# IO_bottom_board.net
KiCad netlist of a schematic drawn in EAGLE
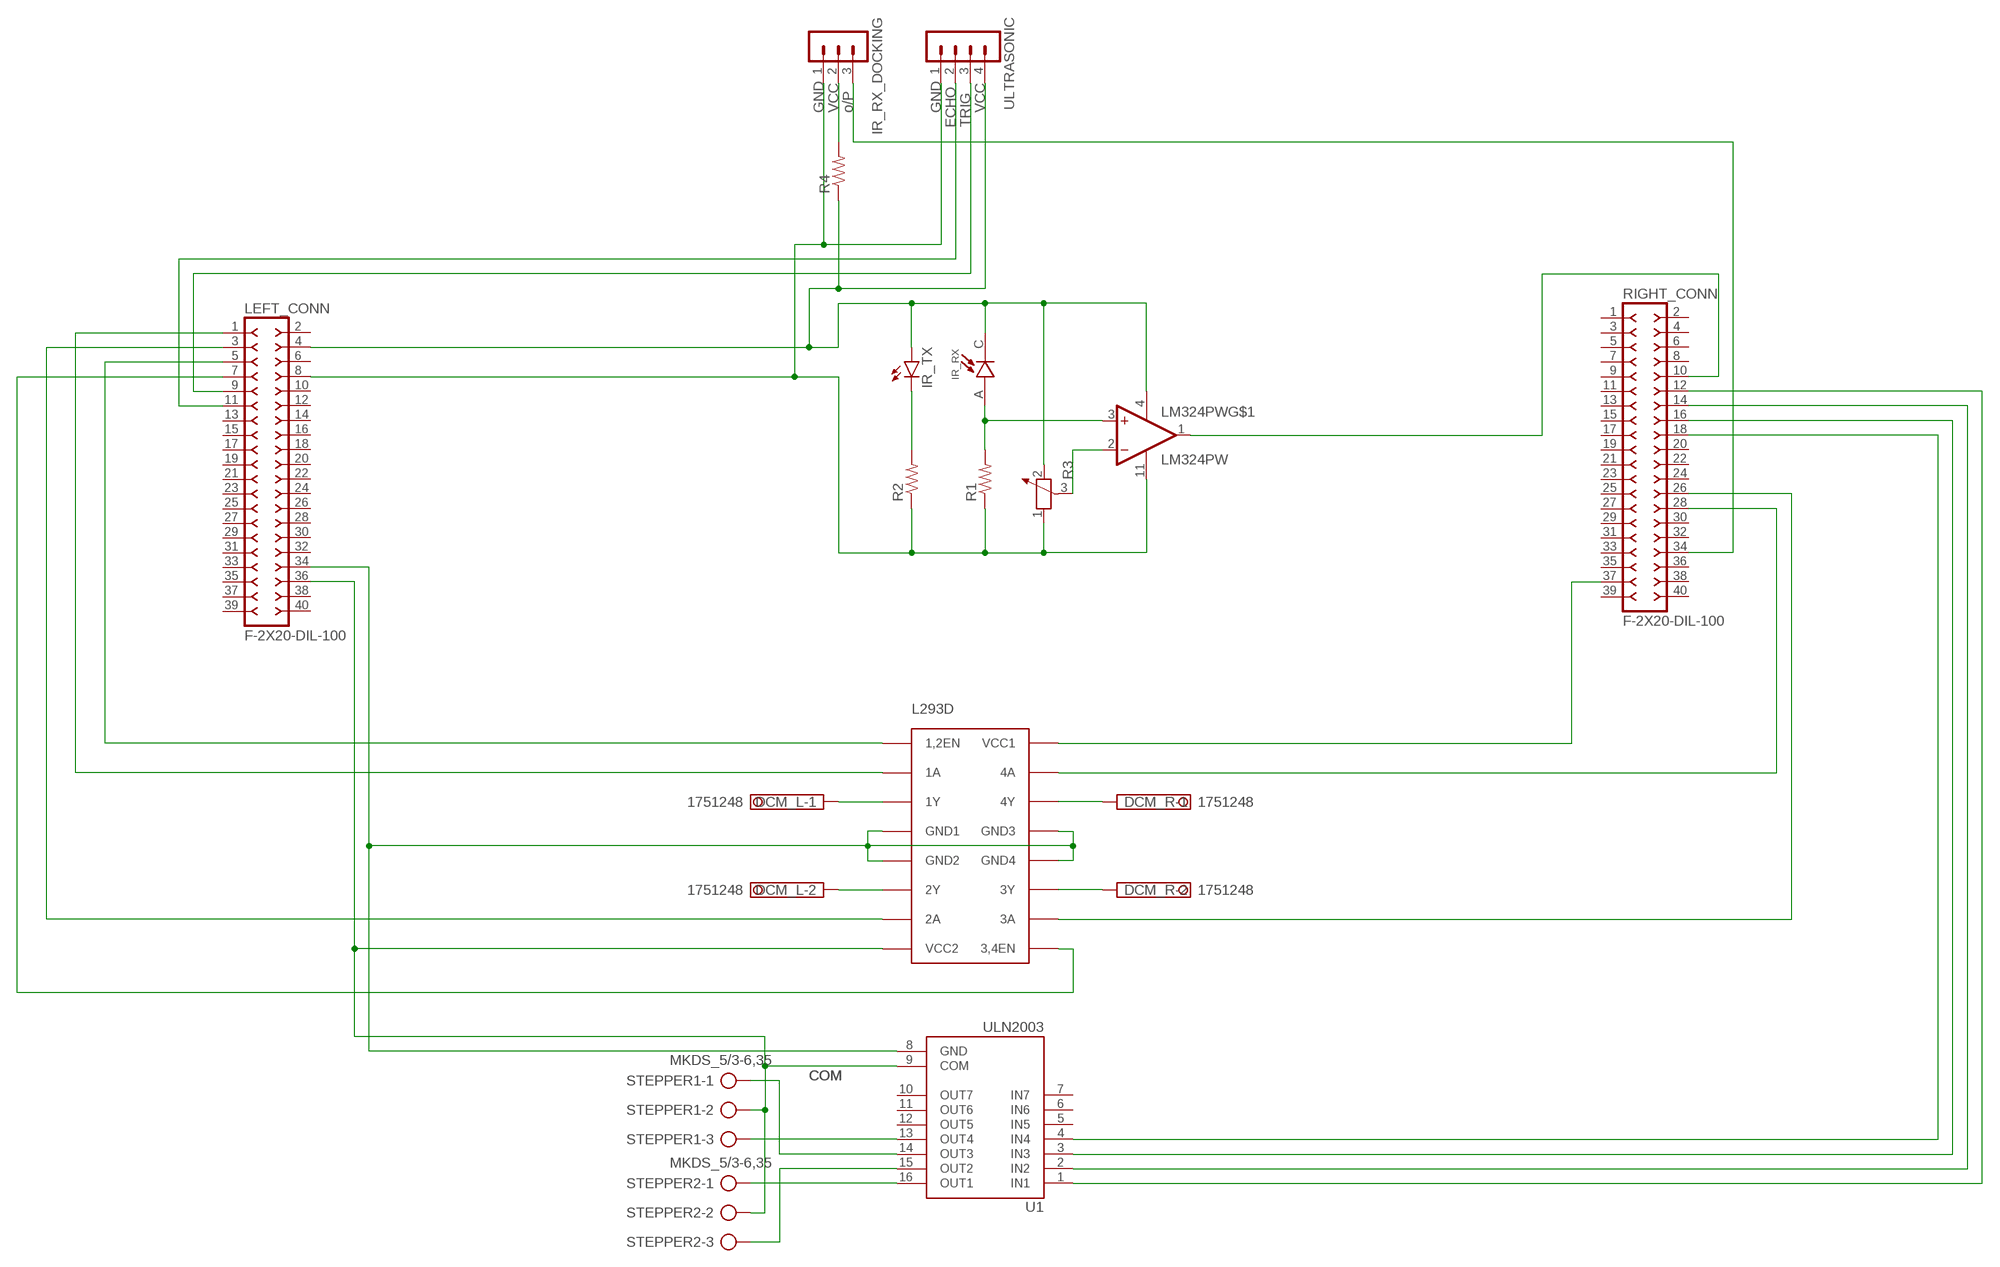
[diagram p0: schematic, sheet 1]

(export (version "E")
  (design (tool "Eeschema 10.0.6"))
  (components
    (comp (ref "DCM_L")
      (value "1751248")
      (footprint "eagle-import:1751248")
      (libsource (lib "eagle-import") (part "1751248"))
    )
    (comp (ref "DCM_R")
      (value "1751248")
      (footprint "eagle-import:1751248")
      (libsource (lib "eagle-import") (part "1751248"))
    )
    (comp (ref "IR_RX")
      (value "BPV10")
      (footprint "eagle-import:XDCR_BPV10")
      (fields (field (name "MF") "Vishay"))
      (libsource (lib "eagle-import") (part "BPV10"))
    )
    (comp (ref "IR_RX_DOCKING")
      (value "MA03-1")
      (footprint "eagle-import:MA03-1")
      (libsource (lib "eagle-import") (part "MA03-1"))
    )
    (comp (ref "IR_TX")
      (value "SFH482")
      (footprint "eagle-import:SFH482")
      (libsource (lib "eagle-import") (part "SFH482"))
    )
    (comp (ref "L293D")
      (value "L293D")
      (footprint "eagle-import:DIL16")
      (libsource (lib "eagle-import") (part "L293D"))
    )
    (comp (ref "LEFT_CONN")
      (value "F-2X20-DIL-100")
      (footprint "eagle-import:DIL-100-2X20")
      (libsource (lib "eagle-import") (part "F-2X20-DIL-100"))
    )
    (comp (ref "LM324PW")
      (value "LM324PW")
      (footprint "eagle-import:SOP65P640X120-14N")
      (fields (field (name "MF") "Texas Instruments"))
      (libsource (lib "eagle-import") (part "LM324PW"))
    )
    (comp (ref "R1")
      (value "R-US_0204/5")
      (footprint "eagle-import:0204_5")
      (libsource (lib "eagle-import") (part "R-US_0204/5"))
    )
    (comp (ref "R2")
      (value "R-US_0204/5")
      (footprint "eagle-import:0204_5")
      (libsource (lib "eagle-import") (part "R-US_0204/5"))
    )
    (comp (ref "R3")
      (value "POTENTIOMETER_PT-10")
      (footprint "eagle-import:PT-10")
      (libsource (lib "eagle-import") (part "POTENTIOMETER_PT-10"))
    )
    (comp (ref "R4")
      (value "R-US_0204/5")
      (footprint "eagle-import:0204_5")
      (libsource (lib "eagle-import") (part "R-US_0204/5"))
    )
    (comp (ref "RIGHT_CONN")
      (value "F-2X20-DIL-100")
      (footprint "eagle-import:DIL-100-2X20")
      (libsource (lib "eagle-import") (part "F-2X20-DIL-100"))
    )
    (comp (ref "STEPPER1")
      (value "MKDS_5/3-6,35")
      (footprint "eagle-import:MKDS_5_3-635")
      (fields (field (name "MF") "FARNELL") (field (name "MPN") "1714968"))
      (libsource (lib "eagle-import") (part "MKDS_5/3-6,35"))
    )
    (comp (ref "STEPPER2")
      (value "MKDS_5/3-6,35")
      (footprint "eagle-import:MKDS_5_3-635")
      (fields (field (name "MF") "FARNELL") (field (name "MPN") "1714968"))
      (libsource (lib "eagle-import") (part "MKDS_5/3-6,35"))
    )
    (comp (ref "U1")
      (value "ULN2003")
      (footprint "eagle-import:DIP762W46P254L1969H533Q16")
      (fields (field (name "MF") "STMicroelectronics"))
      (libsource (lib "eagle-import") (part "ULN2003"))
    )
    (comp (ref "ULTRASONIC")
      (value "MA04-1")
      (footprint "eagle-import:MA04-1")
      (libsource (lib "eagle-import") (part "MA04-1"))
    )
  )
  (nets
    (net (code "1") (name "Net-(DCM_LA-K)") (class "Default")
      (node (ref "DCM_L") (pin "1") (pinfunction "K_1") (pintype "passive"))
      (node (ref "L293D") (pin "3") (pinfunction "1Y_3") (pintype "output"))
    )
    (net (code "2") (name "Net-(DCM_LB-K)") (class "Default")
      (node (ref "DCM_L") (pin "2") (pinfunction "K_2") (pintype "passive"))
      (node (ref "L293D") (pin "6") (pinfunction "2Y_6") (pintype "output"))
    )
    (net (code "3") (name "Net-(DCM_RA-K)") (class "Default")
      (node (ref "DCM_R") (pin "1") (pinfunction "K_1") (pintype "passive"))
      (node (ref "L293D") (pin "14") (pinfunction "4Y_14") (pintype "output"))
    )
    (net (code "4") (name "Net-(DCM_RB-K)") (class "Default")
      (node (ref "DCM_R") (pin "2") (pinfunction "K_2") (pintype "passive"))
      (node (ref "L293D") (pin "11") (pinfunction "3Y_11") (pintype "output"))
    )
    (net (code "5") (name "Net-(IR_RX_DOCKING-Pad2)") (class "Default")
      (node (ref "IR_RX_DOCKING") (pin "2") (pinfunction "2_2") (pintype "passive"))
      (node (ref "R4") (pin "2") (pinfunction "2_2") (pintype "passive"))
    )
    (net (code "6") (name "Net-(IR_RX_DOCKING-Pad3)") (class "Default")
      (node (ref "IR_RX_DOCKING") (pin "3") (pinfunction "3_3") (pintype "passive"))
      (node (ref "RIGHT_CONN") (pin "34") (pinfunction "34_34") (pintype "passive"))
    )
    (net (code "7") (name "Net-(IR_TX-C)") (class "Default")
      (node (ref "IR_TX") (pin "K") (pinfunction "C_K") (pintype "passive"))
      (node (ref "R2") (pin "2") (pinfunction "2_2") (pintype "passive"))
    )
    (net (code "8") (name "Net-(L293D-1,2EN)") (class "Default")
      (node (ref "L293D") (pin "1") (pinfunction "1,2EN_1") (pintype "input"))
      (node (ref "LEFT_CONN") (pin "5") (pinfunction "5_5") (pintype "passive"))
    )
    (net (code "9") (name "Net-(L293D-1A)") (class "Default")
      (node (ref "L293D") (pin "2") (pinfunction "1A_2") (pintype "input"))
      (node (ref "LEFT_CONN") (pin "1") (pinfunction "1_1") (pintype "passive"))
    )
    (net (code "10") (name "Net-(L293D-2A)") (class "Default")
      (node (ref "L293D") (pin "7") (pinfunction "2A_7") (pintype "input"))
      (node (ref "LEFT_CONN") (pin "3") (pinfunction "3_3") (pintype "passive"))
    )
    (net (code "11") (name "Net-(L293D-3,4EN)") (class "Default")
      (node (ref "L293D") (pin "9") (pinfunction "3,4EN_9") (pintype "input"))
      (node (ref "LEFT_CONN") (pin "7") (pinfunction "7_7") (pintype "passive"))
    )
    (net (code "12") (name "Net-(L293D-3A)") (class "Default")
      (node (ref "L293D") (pin "10") (pinfunction "3A_10") (pintype "input"))
      (node (ref "RIGHT_CONN") (pin "26") (pinfunction "26_26") (pintype "passive"))
    )
    (net (code "13") (name "Net-(L293D-4A)") (class "Default")
      (node (ref "L293D") (pin "15") (pinfunction "4A_15") (pintype "input"))
      (node (ref "RIGHT_CONN") (pin "28") (pinfunction "28_28") (pintype "passive"))
    )
    (net (code "14") (name "Net-(L293D-GND1)") (class "Default")
      (node (ref "L293D") (pin "12") (pinfunction "GND4_12") (pintype "power_in"))
      (node (ref "L293D") (pin "13") (pinfunction "GND3_13") (pintype "power_in"))
      (node (ref "L293D") (pin "4") (pinfunction "GND1_4") (pintype "power_in"))
      (node (ref "L293D") (pin "5") (pinfunction "GND2_5") (pintype "power_in"))
      (node (ref "LEFT_CONN") (pin "34") (pinfunction "34_34") (pintype "passive"))
      (node (ref "U1") (pin "8") (pinfunction "GND_8") (pintype "power_in"))
    )
    (net (code "15") (name "Net-(L293D-VCC1)") (class "Default")
      (node (ref "L293D") (pin "16") (pinfunction "VCC1_16") (pintype "power_in"))
      (node (ref "RIGHT_CONN") (pin "37") (pinfunction "37_37") (pintype "passive"))
    )
    (net (code "16") (name "Net-(L293D-VCC2)") (class "Default")
      (node (ref "L293D") (pin "8") (pinfunction "VCC2_8") (pintype "power_in"))
      (node (ref "LEFT_CONN") (pin "36") (pinfunction "36_36") (pintype "passive"))
      (node (ref "STEPPER1") (pin "2") (pinfunction "KL_2") (pintype "passive"))
      (node (ref "STEPPER2") (pin "2") (pinfunction "KL_2") (pintype "passive"))
      (node (ref "U1") (pin "9") (pinfunction "COM_9") (pintype "power_in"))
    )
    (net (code "17") (name "Net-(LEFT_CONN-Pad9)") (class "Default")
      (node (ref "LEFT_CONN") (pin "9") (pinfunction "9_9") (pintype "passive"))
      (node (ref "ULTRASONIC") (pin "3") (pinfunction "3_3") (pintype "passive"))
    )
    (net (code "18") (name "Net-(LEFT_CONN-Pad11)") (class "Default")
      (node (ref "LEFT_CONN") (pin "11") (pinfunction "11_11") (pintype "passive"))
      (node (ref "ULTRASONIC") (pin "2") (pinfunction "2_2") (pintype "passive"))
    )
    (net (code "19") (name "Net-(LM324PWA-+IN1)") (class "Default")
      (node (ref "IR_RX") (pin "A") (pinfunction "A_A") (pintype "passive"))
      (node (ref "LM324PW") (pin "3") (pinfunction "+IN1_3") (pintype "input"))
      (node (ref "R1") (pin "2") (pinfunction "2_2") (pintype "passive"))
    )
    (net (code "20") (name "Net-(LM324PWA--IN1)") (class "Default")
      (node (ref "LM324PW") (pin "2") (pinfunction "-IN1_2") (pintype "input"))
      (node (ref "R3") (pin "3") (pinfunction "3_3") (pintype "passive"))
    )
    (net (code "21") (name "Net-(LM324PWA-GND)") (class "Default")
      (node (ref "IR_RX_DOCKING") (pin "1") (pinfunction "1_1") (pintype "passive"))
      (node (ref "LEFT_CONN") (pin "8") (pinfunction "8_8") (pintype "passive"))
      (node (ref "LM324PW") (pin "11") (pinfunction "GND_11") (pintype "power_in"))
      (node (ref "R1") (pin "1") (pinfunction "1_1") (pintype "passive"))
      (node (ref "R2") (pin "1") (pinfunction "1_1") (pintype "passive"))
      (node (ref "R3") (pin "1") (pinfunction "1_1") (pintype "passive"))
      (node (ref "ULTRASONIC") (pin "1") (pinfunction "1_1") (pintype "passive"))
    )
    (net (code "22") (name "Net-(LM324PWA-OUT1)") (class "Default")
      (node (ref "LM324PW") (pin "1") (pinfunction "OUT1_1") (pintype "output"))
      (node (ref "RIGHT_CONN") (pin "10") (pinfunction "10_10") (pintype "passive"))
    )
    (net (code "23") (name "Net-(LM324PWA-VCC)") (class "Default")
      (node (ref "IR_RX") (pin "C") (pinfunction "C_C") (pintype "passive"))
      (node (ref "IR_TX") (pin "A") (pinfunction "A_A") (pintype "passive"))
      (node (ref "LEFT_CONN") (pin "4") (pinfunction "4_4") (pintype "passive"))
      (node (ref "LM324PW") (pin "4") (pinfunction "VCC_4") (pintype "power_in"))
      (node (ref "R3") (pin "2") (pinfunction "2_2") (pintype "passive"))
      (node (ref "R4") (pin "1") (pinfunction "1_1") (pintype "passive"))
      (node (ref "ULTRASONIC") (pin "4") (pinfunction "4_4") (pintype "passive"))
    )
    (net (code "24") (name "Net-(STEPPER1A-KL)") (class "Default")
      (node (ref "STEPPER1") (pin "1") (pinfunction "KL_1") (pintype "passive"))
      (node (ref "U1") (pin "14") (pinfunction "OUT3_14") (pintype "output"))
    )
    (net (code "25") (name "Net-(STEPPER1C-KL)") (class "Default")
      (node (ref "STEPPER1") (pin "3") (pinfunction "KL_3") (pintype "passive"))
      (node (ref "U1") (pin "13") (pinfunction "OUT4_13") (pintype "output"))
    )
    (net (code "26") (name "Net-(STEPPER2A-KL)") (class "Default")
      (node (ref "STEPPER2") (pin "1") (pinfunction "KL_1") (pintype "passive"))
      (node (ref "U1") (pin "16") (pinfunction "OUT1_16") (pintype "output"))
    )
    (net (code "27") (name "Net-(STEPPER2C-KL)") (class "Default")
      (node (ref "STEPPER2") (pin "3") (pinfunction "KL_3") (pintype "passive"))
      (node (ref "U1") (pin "15") (pinfunction "OUT2_15") (pintype "output"))
    )
    (net (code "28") (name "Net-(U1-IN1)") (class "Default")
      (node (ref "RIGHT_CONN") (pin "12") (pinfunction "12_12") (pintype "passive"))
      (node (ref "U1") (pin "1") (pinfunction "IN1_1") (pintype "input"))
    )
    (net (code "29") (name "Net-(U1-IN2)") (class "Default")
      (node (ref "RIGHT_CONN") (pin "14") (pinfunction "14_14") (pintype "passive"))
      (node (ref "U1") (pin "2") (pinfunction "IN2_2") (pintype "input"))
    )
    (net (code "30") (name "Net-(U1-IN3)") (class "Default")
      (node (ref "RIGHT_CONN") (pin "16") (pinfunction "16_16") (pintype "passive"))
      (node (ref "U1") (pin "3") (pinfunction "IN3_3") (pintype "input"))
    )
    (net (code "31") (name "Net-(U1-IN4)") (class "Default")
      (node (ref "RIGHT_CONN") (pin "18") (pinfunction "18_18") (pintype "passive"))
      (node (ref "U1") (pin "4") (pinfunction "IN4_4") (pintype "input"))
    )
    (net (code "32") (name "unconnected-(LEFT_CONN-Pad2)") (class "Default")
      (node (ref "LEFT_CONN") (pin "2") (pinfunction "2_2") (pintype "passive"))
    )
    (net (code "33") (name "unconnected-(LEFT_CONN-Pad6)") (class "Default")
      (node (ref "LEFT_CONN") (pin "6") (pinfunction "6_6") (pintype "passive"))
    )
    (net (code "34") (name "unconnected-(LEFT_CONN-Pad10)") (class "Default")
      (node (ref "LEFT_CONN") (pin "10") (pinfunction "10_10") (pintype "passive"))
    )
    (net (code "35") (name "unconnected-(LEFT_CONN-Pad12)") (class "Default")
      (node (ref "LEFT_CONN") (pin "12") (pinfunction "12_12") (pintype "passive"))
    )
    (net (code "36") (name "unconnected-(LEFT_CONN-Pad13)") (class "Default")
      (node (ref "LEFT_CONN") (pin "13") (pinfunction "13_13") (pintype "passive"))
    )
    (net (code "37") (name "unconnected-(LEFT_CONN-Pad14)") (class "Default")
      (node (ref "LEFT_CONN") (pin "14") (pinfunction "14_14") (pintype "passive"))
    )
    (net (code "38") (name "unconnected-(LEFT_CONN-Pad15)") (class "Default")
      (node (ref "LEFT_CONN") (pin "15") (pinfunction "15_15") (pintype "passive"))
    )
    (net (code "39") (name "unconnected-(LEFT_CONN-Pad16)") (class "Default")
      (node (ref "LEFT_CONN") (pin "16") (pinfunction "16_16") (pintype "passive"))
    )
    (net (code "40") (name "unconnected-(LEFT_CONN-Pad17)") (class "Default")
      (node (ref "LEFT_CONN") (pin "17") (pinfunction "17_17") (pintype "passive"))
    )
    (net (code "41") (name "unconnected-(LEFT_CONN-Pad18)") (class "Default")
      (node (ref "LEFT_CONN") (pin "18") (pinfunction "18_18") (pintype "passive"))
    )
    (net (code "42") (name "unconnected-(LEFT_CONN-Pad19)") (class "Default")
      (node (ref "LEFT_CONN") (pin "19") (pinfunction "19_19") (pintype "passive"))
    )
    (net (code "43") (name "unconnected-(LEFT_CONN-Pad20)") (class "Default")
      (node (ref "LEFT_CONN") (pin "20") (pinfunction "20_20") (pintype "passive"))
    )
    (net (code "44") (name "unconnected-(LEFT_CONN-Pad21)") (class "Default")
      (node (ref "LEFT_CONN") (pin "21") (pinfunction "21_21") (pintype "passive"))
    )
    (net (code "45") (name "unconnected-(LEFT_CONN-Pad22)") (class "Default")
      (node (ref "LEFT_CONN") (pin "22") (pinfunction "22_22") (pintype "passive"))
    )
    (net (code "46") (name "unconnected-(LEFT_CONN-Pad23)") (class "Default")
      (node (ref "LEFT_CONN") (pin "23") (pinfunction "23_23") (pintype "passive"))
    )
    (net (code "47") (name "unconnected-(LEFT_CONN-Pad24)") (class "Default")
      (node (ref "LEFT_CONN") (pin "24") (pinfunction "24_24") (pintype "passive"))
    )
    (net (code "48") (name "unconnected-(LEFT_CONN-Pad25)") (class "Default")
      (node (ref "LEFT_CONN") (pin "25") (pinfunction "25_25") (pintype "passive"))
    )
    (net (code "49") (name "unconnected-(LEFT_CONN-Pad26)") (class "Default")
      (node (ref "LEFT_CONN") (pin "26") (pinfunction "26_26") (pintype "passive"))
    )
    (net (code "50") (name "unconnected-(LEFT_CONN-Pad27)") (class "Default")
      (node (ref "LEFT_CONN") (pin "27") (pinfunction "27_27") (pintype "passive"))
    )
    (net (code "51") (name "unconnected-(LEFT_CONN-Pad28)") (class "Default")
      (node (ref "LEFT_CONN") (pin "28") (pinfunction "28_28") (pintype "passive"))
    )
    (net (code "52") (name "unconnected-(LEFT_CONN-Pad29)") (class "Default")
      (node (ref "LEFT_CONN") (pin "29") (pinfunction "29_29") (pintype "passive"))
    )
    (net (code "53") (name "unconnected-(LEFT_CONN-Pad30)") (class "Default")
      (node (ref "LEFT_CONN") (pin "30") (pinfunction "30_30") (pintype "passive"))
    )
    (net (code "54") (name "unconnected-(LEFT_CONN-Pad31)") (class "Default")
      (node (ref "LEFT_CONN") (pin "31") (pinfunction "31_31") (pintype "passive"))
    )
    (net (code "55") (name "unconnected-(LEFT_CONN-Pad32)") (class "Default")
      (node (ref "LEFT_CONN") (pin "32") (pinfunction "32_32") (pintype "passive"))
    )
    (net (code "56") (name "unconnected-(LEFT_CONN-Pad33)") (class "Default")
      (node (ref "LEFT_CONN") (pin "33") (pinfunction "33_33") (pintype "passive"))
    )
    (net (code "57") (name "unconnected-(LEFT_CONN-Pad35)") (class "Default")
      (node (ref "LEFT_CONN") (pin "35") (pinfunction "35_35") (pintype "passive"))
    )
    (net (code "58") (name "unconnected-(LEFT_CONN-Pad37)") (class "Default")
      (node (ref "LEFT_CONN") (pin "37") (pinfunction "37_37") (pintype "passive"))
    )
    (net (code "59") (name "unconnected-(LEFT_CONN-Pad38)") (class "Default")
      (node (ref "LEFT_CONN") (pin "38") (pinfunction "38_38") (pintype "passive"))
    )
    (net (code "60") (name "unconnected-(LEFT_CONN-Pad39)") (class "Default")
      (node (ref "LEFT_CONN") (pin "39") (pinfunction "39_39") (pintype "passive"))
    )
    (net (code "61") (name "unconnected-(LEFT_CONN-Pad40)") (class "Default")
      (node (ref "LEFT_CONN") (pin "40") (pinfunction "40_40") (pintype "passive"))
    )
    (net (code "62") (name "unconnected-(RIGHT_CONN-Pad1)") (class "Default")
      (node (ref "RIGHT_CONN") (pin "1") (pinfunction "1_1") (pintype "passive"))
    )
    (net (code "63") (name "unconnected-(RIGHT_CONN-Pad2)") (class "Default")
      (node (ref "RIGHT_CONN") (pin "2") (pinfunction "2_2") (pintype "passive"))
    )
    (net (code "64") (name "unconnected-(RIGHT_CONN-Pad3)") (class "Default")
      (node (ref "RIGHT_CONN") (pin "3") (pinfunction "3_3") (pintype "passive"))
    )
    (net (code "65") (name "unconnected-(RIGHT_CONN-Pad4)") (class "Default")
      (node (ref "RIGHT_CONN") (pin "4") (pinfunction "4_4") (pintype "passive"))
    )
    (net (code "66") (name "unconnected-(RIGHT_CONN-Pad5)") (class "Default")
      (node (ref "RIGHT_CONN") (pin "5") (pinfunction "5_5") (pintype "passive"))
    )
    (net (code "67") (name "unconnected-(RIGHT_CONN-Pad6)") (class "Default")
      (node (ref "RIGHT_CONN") (pin "6") (pinfunction "6_6") (pintype "passive"))
    )
    (net (code "68") (name "unconnected-(RIGHT_CONN-Pad7)") (class "Default")
      (node (ref "RIGHT_CONN") (pin "7") (pinfunction "7_7") (pintype "passive"))
    )
    (net (code "69") (name "unconnected-(RIGHT_CONN-Pad8)") (class "Default")
      (node (ref "RIGHT_CONN") (pin "8") (pinfunction "8_8") (pintype "passive"))
    )
    (net (code "70") (name "unconnected-(RIGHT_CONN-Pad9)") (class "Default")
      (node (ref "RIGHT_CONN") (pin "9") (pinfunction "9_9") (pintype "passive"))
    )
    (net (code "71") (name "unconnected-(RIGHT_CONN-Pad11)") (class "Default")
      (node (ref "RIGHT_CONN") (pin "11") (pinfunction "11_11") (pintype "passive"))
    )
    (net (code "72") (name "unconnected-(RIGHT_CONN-Pad13)") (class "Default")
      (node (ref "RIGHT_CONN") (pin "13") (pinfunction "13_13") (pintype "passive"))
    )
    (net (code "73") (name "unconnected-(RIGHT_CONN-Pad15)") (class "Default")
      (node (ref "RIGHT_CONN") (pin "15") (pinfunction "15_15") (pintype "passive"))
    )
    (net (code "74") (name "unconnected-(RIGHT_CONN-Pad17)") (class "Default")
      (node (ref "RIGHT_CONN") (pin "17") (pinfunction "17_17") (pintype "passive"))
    )
    (net (code "75") (name "unconnected-(RIGHT_CONN-Pad19)") (class "Default")
      (node (ref "RIGHT_CONN") (pin "19") (pinfunction "19_19") (pintype "passive"))
    )
    (net (code "76") (name "unconnected-(RIGHT_CONN-Pad20)") (class "Default")
      (node (ref "RIGHT_CONN") (pin "20") (pinfunction "20_20") (pintype "passive"))
    )
    (net (code "77") (name "unconnected-(RIGHT_CONN-Pad21)") (class "Default")
      (node (ref "RIGHT_CONN") (pin "21") (pinfunction "21_21") (pintype "passive"))
    )
    (net (code "78") (name "unconnected-(RIGHT_CONN-Pad22)") (class "Default")
      (node (ref "RIGHT_CONN") (pin "22") (pinfunction "22_22") (pintype "passive"))
    )
    (net (code "79") (name "unconnected-(RIGHT_CONN-Pad23)") (class "Default")
      (node (ref "RIGHT_CONN") (pin "23") (pinfunction "23_23") (pintype "passive"))
    )
    (net (code "80") (name "unconnected-(RIGHT_CONN-Pad24)") (class "Default")
      (node (ref "RIGHT_CONN") (pin "24") (pinfunction "24_24") (pintype "passive"))
    )
    (net (code "81") (name "unconnected-(RIGHT_CONN-Pad25)") (class "Default")
      (node (ref "RIGHT_CONN") (pin "25") (pinfunction "25_25") (pintype "passive"))
    )
    (net (code "82") (name "unconnected-(RIGHT_CONN-Pad27)") (class "Default")
      (node (ref "RIGHT_CONN") (pin "27") (pinfunction "27_27") (pintype "passive"))
    )
    (net (code "83") (name "unconnected-(RIGHT_CONN-Pad29)") (class "Default")
      (node (ref "RIGHT_CONN") (pin "29") (pinfunction "29_29") (pintype "passive"))
    )
    (net (code "84") (name "unconnected-(RIGHT_CONN-Pad30)") (class "Default")
      (node (ref "RIGHT_CONN") (pin "30") (pinfunction "30_30") (pintype "passive"))
    )
    (net (code "85") (name "unconnected-(RIGHT_CONN-Pad31)") (class "Default")
      (node (ref "RIGHT_CONN") (pin "31") (pinfunction "31_31") (pintype "passive"))
    )
    (net (code "86") (name "unconnected-(RIGHT_CONN-Pad32)") (class "Default")
      (node (ref "RIGHT_CONN") (pin "32") (pinfunction "32_32") (pintype "passive"))
    )
    (net (code "87") (name "unconnected-(RIGHT_CONN-Pad33)") (class "Default")
      (node (ref "RIGHT_CONN") (pin "33") (pinfunction "33_33") (pintype "passive"))
    )
    (net (code "88") (name "unconnected-(RIGHT_CONN-Pad35)") (class "Default")
      (node (ref "RIGHT_CONN") (pin "35") (pinfunction "35_35") (pintype "passive"))
    )
    (net (code "89") (name "unconnected-(RIGHT_CONN-Pad36)") (class "Default")
      (node (ref "RIGHT_CONN") (pin "36") (pinfunction "36_36") (pintype "passive"))
    )
    (net (code "90") (name "unconnected-(RIGHT_CONN-Pad38)") (class "Default")
      (node (ref "RIGHT_CONN") (pin "38") (pinfunction "38_38") (pintype "passive"))
    )
    (net (code "91") (name "unconnected-(RIGHT_CONN-Pad39)") (class "Default")
      (node (ref "RIGHT_CONN") (pin "39") (pinfunction "39_39") (pintype "passive"))
    )
    (net (code "92") (name "unconnected-(RIGHT_CONN-Pad40)") (class "Default")
      (node (ref "RIGHT_CONN") (pin "40") (pinfunction "40_40") (pintype "passive"))
    )
    (net (code "93") (name "unconnected-(U1-IN5-Pad5)") (class "Default")
      (node (ref "U1") (pin "5") (pinfunction "IN5_5") (pintype "input"))
    )
    (net (code "94") (name "unconnected-(U1-IN6-Pad6)") (class "Default")
      (node (ref "U1") (pin "6") (pinfunction "IN6_6") (pintype "input"))
    )
    (net (code "95") (name "unconnected-(U1-IN7-Pad7)") (class "Default")
      (node (ref "U1") (pin "7") (pinfunction "IN7_7") (pintype "input"))
    )
    (net (code "96") (name "unconnected-(U1-OUT5-Pad12)") (class "Default")
      (node (ref "U1") (pin "12") (pinfunction "OUT5_12") (pintype "output"))
    )
    (net (code "97") (name "unconnected-(U1-OUT6-Pad11)") (class "Default")
      (node (ref "U1") (pin "11") (pinfunction "OUT6_11") (pintype "output"))
    )
    (net (code "98") (name "unconnected-(U1-OUT7-Pad10)") (class "Default")
      (node (ref "U1") (pin "10") (pinfunction "OUT7_10") (pintype "output"))
    )
  )
)
